# CH32V307V-R0-1v0.net
KiCad netlist of a schematic drawn in Altium Designer
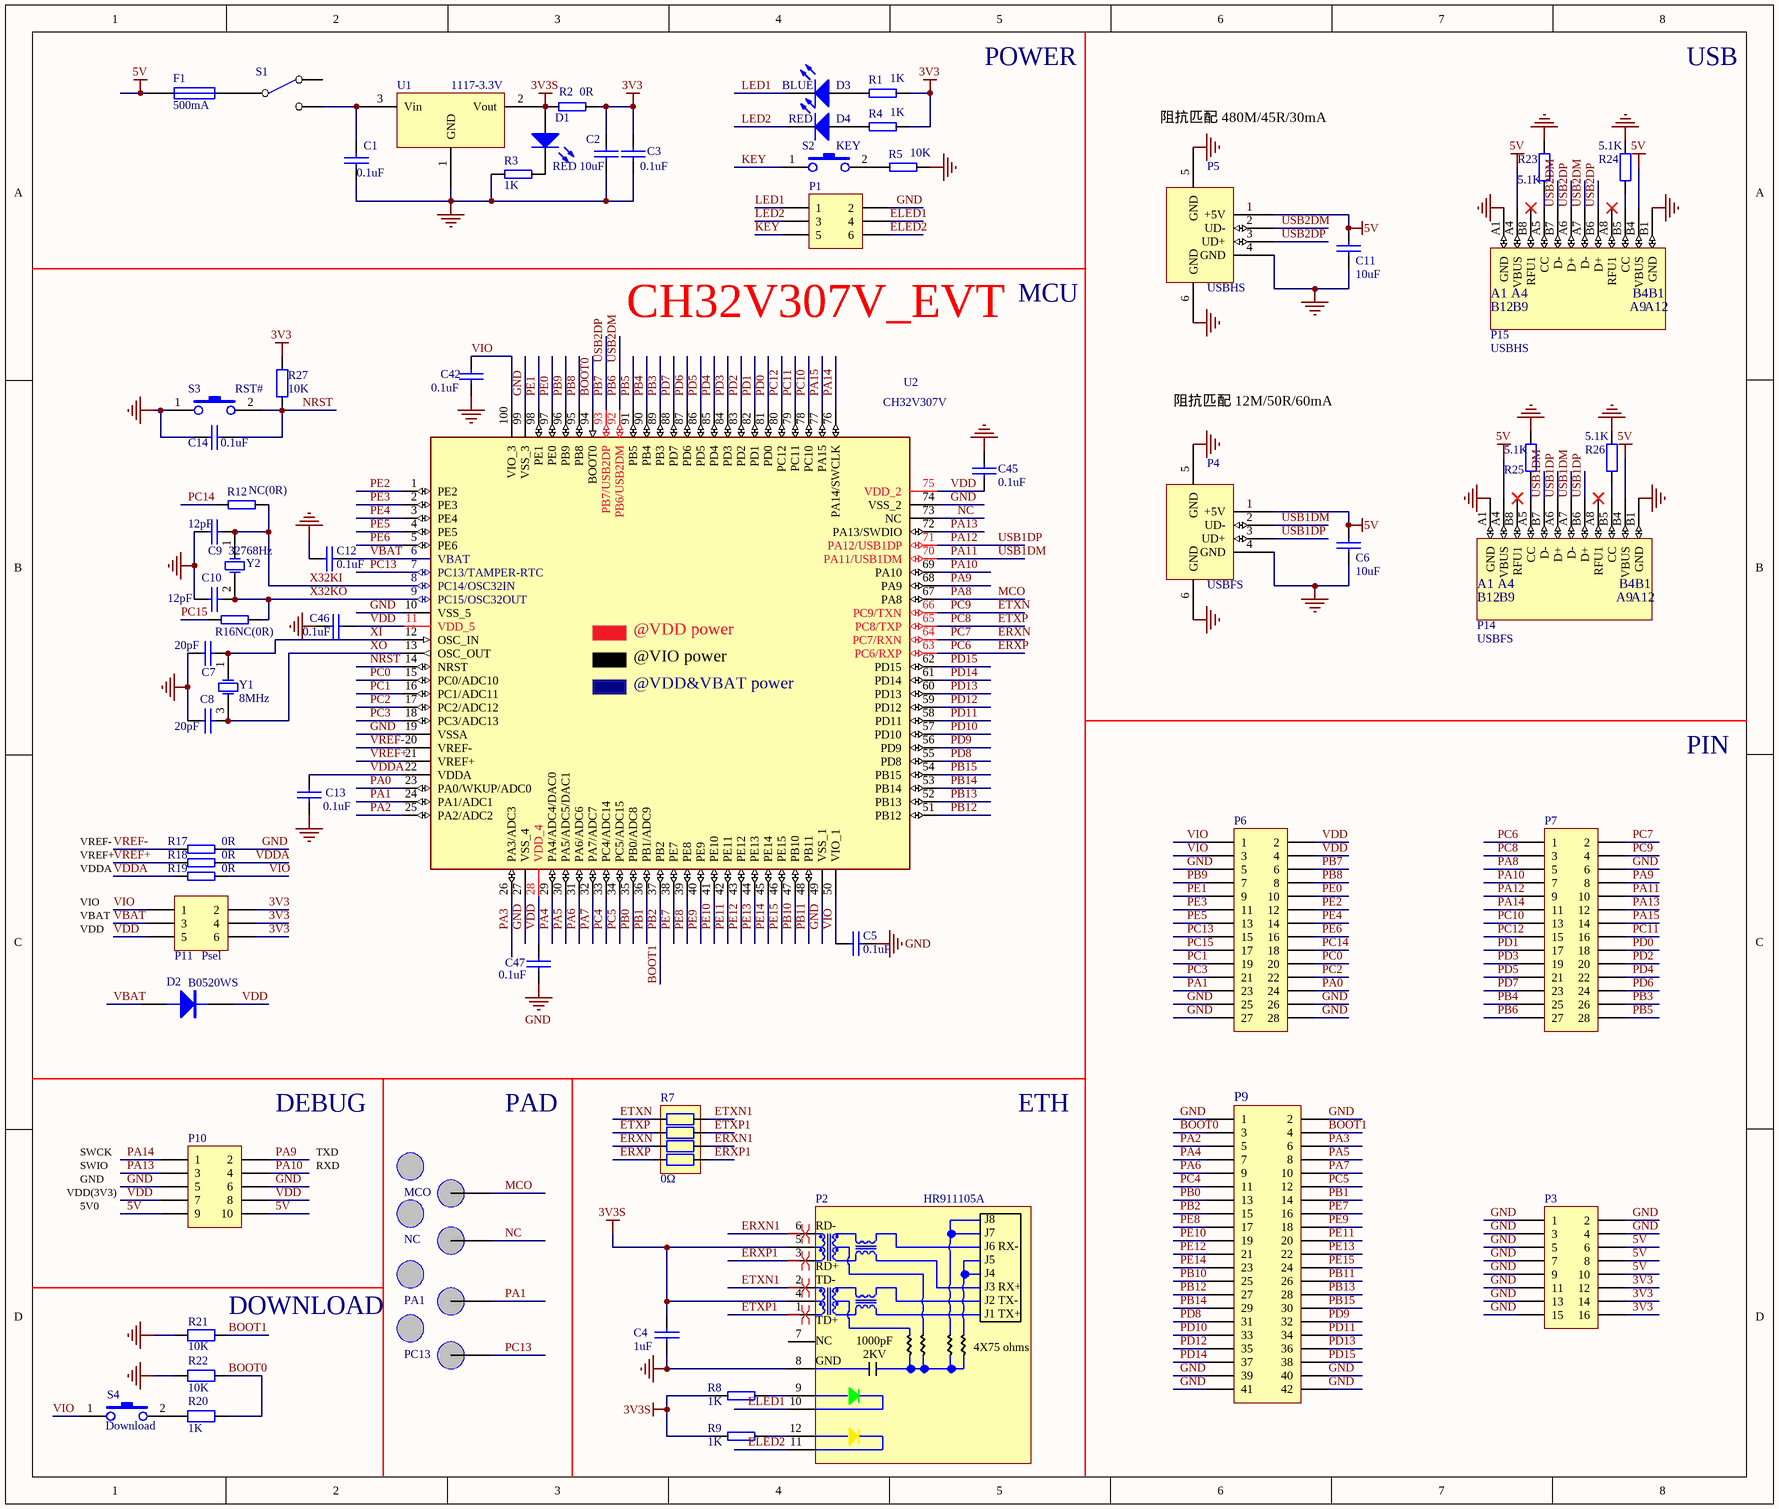
[diagram p0: CH32V307V-R0-1v0.SchDoc]

(export (version "E")
  (design (tool "Eeschema 10.0.6"))
  (components
    (comp (ref "C1")
      (value "0.1uF")
      (footprint "0603_C")
      (description "Capacitor")
      (libsource (lib "*") (part "CAP"))
    )
    (comp (ref "C2")
      (value "10uF")
      (footprint "3216_C")
      (description "Capacitor")
      (libsource (lib "*") (part "CAP"))
    )
    (comp (ref "C3")
      (value "0.1uF")
      (footprint "0603_C")
      (description "Capacitor")
      (libsource (lib "*") (part "CAP"))
    )
    (comp (ref "C4")
      (value "1uF")
      (footprint "0603_C")
      (description "Capacitor")
      (libsource (lib "*") (part "CAP"))
    )
    (comp (ref "C5")
      (value "0.1uF")
      (footprint "0603_C")
      (description "Capacitor")
      (libsource (lib "*") (part "CAP"))
    )
    (comp (ref "C6")
      (value "10uF")
      (footprint "3216_C")
      (description "Capacitor")
      (libsource (lib "") (part "CAP_1"))
    )
    (comp (ref "C7")
      (value "20pF")
      (footprint "0603_C")
      (description "Capacitor")
      (libsource (lib "*") (part "CAP"))
    )
    (comp (ref "C8")
      (value "20pF")
      (footprint "0603_C")
      (description "Capacitor")
      (libsource (lib "*") (part "CAP"))
    )
    (comp (ref "C9")
      (value "12pF")
      (footprint "0603_C")
      (description "Capacitor")
      (libsource (lib "*") (part "CAP"))
    )
    (comp (ref "C10")
      (value "12pF")
      (footprint "0603_C")
      (description "Capacitor")
      (libsource (lib "*") (part "CAP"))
    )
    (comp (ref "C11")
      (value "10uF")
      (footprint "3216_C")
      (description "Capacitor")
      (libsource (lib "") (part "CAP_1"))
    )
    (comp (ref "C12")
      (value "0.1uF")
      (footprint "0603_C")
      (description "Capacitor")
      (libsource (lib "*") (part "CAP"))
    )
    (comp (ref "C13")
      (value "0.1uF")
      (footprint "0603_C")
      (description "Capacitor")
      (libsource (lib "*") (part "CAP"))
    )
    (comp (ref "C14")
      (value "0.1uF")
      (footprint "0603_C")
      (description "Capacitor")
      (libsource (lib "") (part "CAP_1"))
    )
    (comp (ref "C42")
      (value "0.1uF")
      (footprint "0603_C")
      (description "Capacitor")
      (libsource (lib "*") (part "CAP"))
    )
    (comp (ref "C45")
      (value "0.1uF")
      (footprint "0603_C")
      (description "Capacitor")
      (libsource (lib "*") (part "CAP"))
    )
    (comp (ref "C46")
      (value "0.1uF")
      (footprint "0603_C")
      (description "Capacitor")
      (libsource (lib "*") (part "CAP"))
    )
    (comp (ref "C47")
      (value "0.1uF")
      (footprint "0603_C")
      (description "Capacitor")
      (libsource (lib "*") (part "CAP"))
    )
    (comp (ref "D1")
      (value "RED")
      (footprint "0603+")
      (description "Typical INFRARED GaAs LED")
      (fields (field (name "PUBLISHER") "Altium Limited"))
      (libsource (lib "*") (part "LED0"))
    )
    (comp (ref "D2")
      (value "B0520WS")
      (footprint "SOD-323")
      (description "Diode")
      (libsource (lib "*") (part "DIODE"))
    )
    (comp (ref "D3")
      (value "BLUE")
      (footprint "0603+")
      (description "Typical INFRARED GaAs LED")
      (fields (field (name "PUBLISHER") "Altium Limited"))
      (libsource (lib "*") (part "LED0"))
    )
    (comp (ref "D4")
      (value "RED")
      (footprint "0603+")
      (description "Typical INFRARED GaAs LED")
      (fields (field (name "PUBLISHER") "Altium Limited"))
      (libsource (lib "*") (part "LED0"))
    )
    (comp (ref "F1")
      (value "500mA")
      (footprint "0805")
      (description "Fuse")
      (libsource (lib "wch_sch_others") (part "FUSE1"))
    )
    (comp (ref "MCO")
      (value "Testpoint")
      (footprint "TESTPOINT1")
      (description "测试点")
      (libsource (lib "wch_sch_others") (part "Testpoint"))
    )
    (comp (ref "NC")
      (value "Testpoint")
      (footprint "TESTPOINT1")
      (description "测试点")
      (libsource (lib "wch_sch_others") (part "Testpoint"))
    )
    (comp (ref "P1")
      (value "IO")
      (footprint "IDC6-2.54mm")
      (description "Header, 3-Pin, Dual row, Right Angle")
      (fields (field (name "PUBLISHER") "Altium Limited"))
      (libsource (lib "Miscellaneous Connectors") (part "Header 3X2H"))
    )
    (comp (ref "P2") (value "HR911105A") (footprint "HR911105A") (libsource (lib "*") (part "HR911105A")))
    (comp (ref "P3")
      (value "Ppin")
      (footprint "IDC16-2.54mm")
      (description "Header, 8-Pin, Dual row, Right Angle")
      (fields (field (name "PUBLISHER") "Altium Limited"))
      (libsource (lib "Miscellaneous Connectors") (part "Header 8X2H"))
    )
    (comp (ref "P4")
      (value "USBFS")
      (footprint "USBAF")
      (description "USB Port")
      (libsource (lib "*") (part "USB"))
    )
    (comp (ref "P5")
      (value "USBHS")
      (footprint "USBAF")
      (description "USB Port")
      (libsource (lib "*") (part "USB"))
    )
    (comp (ref "P6")
      (value "HEADER 14x2")
      (footprint "MYPCB:IDC28-2.54MM")
      (description "Header, 14-Pin, Dual row")
      (libsource (lib "wch_sch_others") (part "HEADER 14x2"))
    )
    (comp (ref "P7")
      (value "HEADER 14x2")
      (footprint "MYPCB:IDC28-2.54MM")
      (description "Header, 14-Pin, Dual row")
      (libsource (lib "wch_sch_others") (part "HEADER 14x2"))
    )
    (comp (ref "P9")
      (value "HEADER 21x2")
      (footprint "MYPCB:IDC42-2.54MM")
      (description "Header, 21-Pin, Dual row")
      (libsource (lib "wch_sch_others") (part "HEADER 21x2"))
    )
    (comp (ref "P10")
      (value "LINK")
      (footprint "IDC10-2.54mm")
      (description "Header, 5-Pin, Dual row, Right Angle")
      (fields (field (name "PUBLISHER") "Altium Limited"))
      (libsource (lib "Miscellaneous Connectors") (part "Header 5X2H"))
    )
    (comp (ref "P11")
      (value "Psel")
      (footprint "IDC6-2.54mm")
      (description "Header, 3-Pin, Dual row, Right Angle")
      (fields (field (name "PUBLISHER") "Altium Limited"))
      (libsource (lib "Miscellaneous Connectors") (part "Header 3X2H"))
    )
    (comp (ref "P14")
      (value "USBFS")
      (footprint "TYPE-C-Receptacle-2.0")
      (libsource (lib "*") (part "TYPE-C1"))
    )
    (comp (ref "P15")
      (value "USBHS")
      (footprint "TYPE-C-Receptacle-2.0")
      (libsource (lib "*") (part "TYPE-C1"))
    )
    (comp (ref "PA1")
      (value "Testpoint")
      (footprint "TESTPOINT1")
      (description "测试点")
      (libsource (lib "wch_sch_others") (part "Testpoint"))
    )
    (comp (ref "PC13")
      (value "Testpoint")
      (footprint "TESTPOINT1")
      (description "测试点")
      (libsource (lib "wch_sch_others") (part "Testpoint"))
    )
    (comp (ref "R1") (value "1K") (footprint "0603") (libsource (lib "wch_sch_others") (part "RES")))
    (comp (ref "R2") (value "0R") (footprint "0603") (libsource (lib "wch_sch_others") (part "RES")))
    (comp (ref "R3") (value "1K") (footprint "0603") (libsource (lib "wch_sch_others") (part "RES")))
    (comp (ref "R4") (value "1K") (footprint "0603") (libsource (lib "wch_sch_others") (part "RES")))
    (comp (ref "R5") (value "10K") (footprint "0603") (libsource (lib "wch_sch_others") (part "RES")))
    (comp (ref "R7")
      (value "0Ω")
      (footprint "RCA-8P4R-0603")
      (description "贴片网络排阻")
      (fields (field (name "版权归属") "源创客"))
      (libsource (lib "wch_sch_others") (part "R-8P4R"))
    )
    (comp (ref "R8") (value "1K") (footprint "0603") (libsource (lib "wch_sch_others") (part "RES")))
    (comp (ref "R9") (value "1K") (footprint "0603") (libsource (lib "wch_sch_others") (part "RES")))
    (comp (ref "R12") (value "NC(0R)") (footprint "0603") (libsource (lib "wch_sch_others") (part "RES")))
    (comp (ref "R16") (value "NC(0R)") (footprint "0603") (libsource (lib "wch_sch_others") (part "RES")))
    (comp (ref "R17") (value "0R") (footprint "0603") (libsource (lib "*") (part "R")))
    (comp (ref "R18") (value "0R") (footprint "0603") (libsource (lib "*") (part "R")))
    (comp (ref "R19") (value "0R") (footprint "0603") (libsource (lib "*") (part "R")))
    (comp (ref "R20")
      (value "1K")
      (footprint "0603")
      (description "Resistor")
      (fields (field (name "PUBLISHER") "Altium Limited"))
      (libsource (lib "Miscellaneous Devices") (part "Res2"))
    )
    (comp (ref "R21")
      (value "10K")
      (footprint "0603")
      (description "Resistor")
      (fields (field (name "PUBLISHER") "Altium Limited"))
      (libsource (lib "Miscellaneous Devices") (part "Res2"))
    )
    (comp (ref "R22")
      (value "10K")
      (footprint "0603")
      (description "Resistor")
      (fields (field (name "PUBLISHER") "Altium Limited"))
      (libsource (lib "Miscellaneous Devices") (part "Res2"))
    )
    (comp (ref "R23")
      (value "5.1K")
      (footprint "0603")
      (description "Resistor")
      (libsource (lib "") (part "Res2_1"))
    )
    (comp (ref "R24")
      (value "5.1K")
      (footprint "0603")
      (description "Resistor")
      (libsource (lib "") (part "Res2_1"))
    )
    (comp (ref "R25")
      (value "5.1K")
      (footprint "0603")
      (description "Resistor")
      (libsource (lib "") (part "Res2_1"))
    )
    (comp (ref "R26")
      (value "5.1K")
      (footprint "0603")
      (description "Resistor")
      (libsource (lib "") (part "Res2_1"))
    )
    (comp (ref "R27")
      (value "10K")
      (footprint "0603")
      (description "Resistor")
      (fields (field (name "PUBLISHER") "Altium Limited"))
      (libsource (lib "") (part "Res2_1"))
    )
    (comp (ref "S1") (value "SW SPDT") (footprint "KEY_B") (libsource (lib "*") (part "SW SPDT")))
    (comp (ref "S2")
      (value "KEY")
      (footprint "SMD_6.1x3.65x2.5mm-KEY")
      (libsource (lib "wch_sch_others") (part "KEY1"))
    )
    (comp (ref "S3")
      (value "RST#")
      (footprint "SMD_6.1x3.65x2.5mm-KEY")
      (libsource (lib "wch_sch_others") (part "KEY1"))
    )
    (comp (ref "S4")
      (value "Download")
      (footprint "SMD_6.1x3.65x2.5mm-KEY")
      (libsource (lib "wch_sch_others") (part "KEY1"))
    )
    (comp (ref "U1")
      (value "1117-3.3V")
      (footprint "SOT-223")
      (libsource (lib "wch_sch_others") (part "1117-3.3V"))
    )
    (comp (ref "U2")
      (value "CH32V307V")
      (footprint "LQFP100")
      (description "RISC-V FPU MCU, 144MHz, USB_480M，USB OTG,1000M Ethernet MAC, 2*CAN")
      (libsource (lib "CHXXX") (part "CH32V307V"))
    )
    (comp (ref "Y1")
      (value "8MHz")
      (footprint "XT3225")
      (description "Crystal Oscillator")
      (fields (field (name "PUBLISHER") "Altium Limited"))
      (libsource (lib "*") (part "XTAL"))
    )
    (comp (ref "Y2")
      (value "32768Hz")
      (footprint "FC-135")
      (description "Crystal Oscillator")
      (fields (field (name "PUBLISHER") "Altium Limited"))
      (libsource (lib "") (part "XTAL_1"))
    )
  )
  (nets
    (net (code "2") (name "/BOOT0") (class "Default")
      (node (ref "P9") (pin "3") (pinfunction "3_3") (pintype "passive"))
      (node (ref "R20") (pin "1") (pinfunction "1_1") (pintype "passive"))
      (node (ref "R22") (pin "1") (pinfunction "1_1") (pintype "passive"))
      (node (ref "U2") (pin "94") (pinfunction "BOOT0_94") (pintype "input"))
    )
    (net (code "3") (name "/BOOT1") (class "Default")
      (node (ref "P9") (pin "15") (pinfunction "15_15") (pintype "passive"))
      (node (ref "P9") (pin "4") (pinfunction "4_4") (pintype "passive"))
      (node (ref "R21") (pin "1") (pinfunction "1_1") (pintype "passive"))
      (node (ref "U2") (pin "37") (pinfunction "PB2_37") (pintype "bidirectional"))
    )
    (net (code "4") (name "/ELED1") (class "Default")
      (node (ref "P1") (pin "4") (pinfunction "4_4") (pintype "passive"))
      (node (ref "P2") (pin "10") (pintype "passive"))
    )
    (net (code "5") (name "/ELED2") (class "Default")
      (node (ref "P1") (pin "6") (pinfunction "6_6") (pintype "passive"))
      (node (ref "P2") (pin "11") (pintype "passive"))
    )
    (net (code "6") (name "/ERXN") (class "Default")
      (node (ref "P7") (pin "2") (pinfunction "2_2") (pintype "passive"))
      (node (ref "R7") (pin "3") (pinfunction "3_3") (pintype "passive"))
      (node (ref "U2") (pin "64") (pinfunction "PC7/RXN_64") (pintype "bidirectional"))
    )
    (net (code "7") (name "/ERXN1") (class "Default")
      (node (ref "P2") (pin "6") (pintype "passive"))
      (node (ref "R7") (pin "6") (pinfunction "6_6") (pintype "passive"))
    )
    (net (code "8") (name "/ERXP") (class "Default")
      (node (ref "P7") (pin "1") (pinfunction "1_1") (pintype "passive"))
      (node (ref "R7") (pin "4") (pinfunction "4_4") (pintype "passive"))
      (node (ref "U2") (pin "63") (pinfunction "PC6/RXP_63") (pintype "bidirectional"))
    )
    (net (code "9") (name "/ERXP1") (class "Default")
      (node (ref "P2") (pin "3") (pintype "passive"))
      (node (ref "R7") (pin "5") (pinfunction "5_5") (pintype "passive"))
    )
    (net (code "10") (name "/ETXN") (class "Default")
      (node (ref "P7") (pin "4") (pinfunction "4_4") (pintype "passive"))
      (node (ref "R7") (pin "1") (pinfunction "1_1") (pintype "passive"))
      (node (ref "U2") (pin "66") (pinfunction "PC9/TXN_66") (pintype "bidirectional"))
    )
    (net (code "11") (name "/ETXN1") (class "Default")
      (node (ref "P2") (pin "2") (pintype "passive"))
      (node (ref "R7") (pin "8") (pinfunction "8_8") (pintype "passive"))
    )
    (net (code "12") (name "/ETXP") (class "Default")
      (node (ref "P7") (pin "3") (pinfunction "3_3") (pintype "passive"))
      (node (ref "R7") (pin "2") (pinfunction "2_2") (pintype "passive"))
      (node (ref "U2") (pin "65") (pinfunction "PC8/TXP_65") (pintype "bidirectional"))
    )
    (net (code "13") (name "/ETXP1") (class "Default")
      (node (ref "P2") (pin "1") (pintype "passive"))
      (node (ref "R7") (pin "7") (pinfunction "7_7") (pintype "passive"))
    )
    (net (code "14") (name "/KEY") (class "Default")
      (node (ref "P1") (pin "5") (pinfunction "5_5") (pintype "passive"))
      (node (ref "S2") (pin "1") (pinfunction "1_1") (pintype "passive"))
    )
    (net (code "15") (name "/LED1") (class "Default")
      (node (ref "D3") (pin "2") (pinfunction "K_2") (pintype "passive"))
      (node (ref "P1") (pin "1") (pinfunction "1_1") (pintype "passive"))
    )
    (net (code "16") (name "/LED2") (class "Default")
      (node (ref "D4") (pin "2") (pinfunction "K_2") (pintype "passive"))
      (node (ref "P1") (pin "3") (pinfunction "3_3") (pintype "passive"))
    )
    (net (code "17") (name "/MCO") (class "Default")
      (node (ref "MCO") (pin "1") (pinfunction "point_1") (pintype "passive"))
      (node (ref "P7") (pin "5") (pinfunction "5_5") (pintype "passive"))
      (node (ref "U2") (pin "67") (pinfunction "PA8_67") (pintype "bidirectional"))
    )
    (net (code "18") (name "/NC") (class "Default")
      (node (ref "NC") (pin "1") (pinfunction "point_1") (pintype "passive"))
      (node (ref "U2") (pin "73") (pinfunction "NC_73") (pintype "tri_state"))
    )
    (net (code "19") (name "/NRST") (class "Default")
      (node (ref "C14") (pin "2") (pinfunction "2_2") (pintype "passive"))
      (node (ref "R27") (pin "1") (pinfunction "1_1") (pintype "passive"))
      (node (ref "S3") (pin "2") (pinfunction "2_2") (pintype "passive"))
      (node (ref "U2") (pin "14") (pinfunction "NRST_14") (pintype "bidirectional"))
    )
    (net (code "20") (name "/PA0") (class "Default")
      (node (ref "P6") (pin "24") (pinfunction "24_24") (pintype "passive"))
      (node (ref "U2") (pin "23") (pinfunction "PA0/WKUP/ADC0_23") (pintype "bidirectional"))
    )
    (net (code "21") (name "/PA1") (class "Default")
      (node (ref "P6") (pin "23") (pinfunction "23_23") (pintype "passive"))
      (node (ref "PA1") (pin "1") (pinfunction "point_1") (pintype "passive"))
      (node (ref "U2") (pin "24") (pinfunction "PA1/ADC1_24") (pintype "bidirectional"))
    )
    (net (code "22") (name "/PA2") (class "Default")
      (node (ref "P9") (pin "5") (pinfunction "5_5") (pintype "passive"))
      (node (ref "U2") (pin "25") (pinfunction "PA2/ADC2_25") (pintype "bidirectional"))
    )
    (net (code "23") (name "/PA3") (class "Default")
      (node (ref "P9") (pin "6") (pinfunction "6_6") (pintype "passive"))
      (node (ref "U2") (pin "26") (pinfunction "PA3/ADC3_26") (pintype "bidirectional"))
    )
    (net (code "24") (name "/PA4") (class "Default")
      (node (ref "P9") (pin "7") (pinfunction "7_7") (pintype "passive"))
      (node (ref "U2") (pin "29") (pinfunction "PA4/ADC4/DAC0_29") (pintype "bidirectional"))
    )
    (net (code "25") (name "/PA5") (class "Default")
      (node (ref "P9") (pin "8") (pinfunction "8_8") (pintype "passive"))
      (node (ref "U2") (pin "30") (pinfunction "PA5/ADC5/DAC1_30") (pintype "bidirectional"))
    )
    (net (code "26") (name "/PA6") (class "Default")
      (node (ref "P9") (pin "9") (pinfunction "9_9") (pintype "passive"))
      (node (ref "U2") (pin "31") (pinfunction "PA6/ADC6_31") (pintype "bidirectional"))
    )
    (net (code "27") (name "/PA7") (class "Default")
      (node (ref "P9") (pin "10") (pinfunction "10_10") (pintype "passive"))
      (node (ref "U2") (pin "32") (pinfunction "PA7/ADC7_32") (pintype "bidirectional"))
    )
    (net (code "28") (name "/PA9") (class "Default")
      (node (ref "P10") (pin "2") (pinfunction "2_2") (pintype "passive"))
      (node (ref "P7") (pin "8") (pinfunction "8_8") (pintype "passive"))
      (node (ref "U2") (pin "68") (pinfunction "PA9_68") (pintype "bidirectional"))
    )
    (net (code "29") (name "/PA10") (class "Default")
      (node (ref "P10") (pin "4") (pinfunction "4_4") (pintype "passive"))
      (node (ref "P7") (pin "7") (pinfunction "7_7") (pintype "passive"))
      (node (ref "U2") (pin "69") (pinfunction "PA10_69") (pintype "bidirectional"))
    )
    (net (code "30") (name "/PA11") (class "Default")
      (node (ref "P14") (pin "A7") (pinfunction "D-_A7") (pintype "bidirectional"))
      (node (ref "P14") (pin "B7") (pinfunction "D-_B7") (pintype "bidirectional"))
      (node (ref "P4") (pin "2") (pinfunction "UD-_2") (pintype "bidirectional"))
      (node (ref "P7") (pin "10") (pinfunction "10_10") (pintype "passive"))
      (node (ref "U2") (pin "70") (pinfunction "PA11/USB1DM_70") (pintype "bidirectional"))
    )
    (net (code "31") (name "/PA12") (class "Default")
      (node (ref "P14") (pin "A6") (pinfunction "D+_A6") (pintype "bidirectional"))
      (node (ref "P14") (pin "B6") (pinfunction "D+_B6") (pintype "bidirectional"))
      (node (ref "P4") (pin "3") (pinfunction "UD+_3") (pintype "bidirectional"))
      (node (ref "P7") (pin "9") (pinfunction "9_9") (pintype "passive"))
      (node (ref "U2") (pin "71") (pinfunction "PA12/USB1DP_71") (pintype "bidirectional"))
    )
    (net (code "32") (name "/PA13") (class "Default")
      (node (ref "P10") (pin "3") (pinfunction "3_3") (pintype "passive"))
      (node (ref "P7") (pin "12") (pinfunction "12_12") (pintype "passive"))
      (node (ref "U2") (pin "72") (pinfunction "PA13/SWDIO_72") (pintype "bidirectional"))
    )
    (net (code "33") (name "/PA14") (class "Default")
      (node (ref "P10") (pin "1") (pinfunction "1_1") (pintype "passive"))
      (node (ref "P7") (pin "11") (pinfunction "11_11") (pintype "passive"))
      (node (ref "U2") (pin "76") (pinfunction "PA14/SWCLK_76") (pintype "bidirectional"))
    )
    (net (code "34") (name "/PA15") (class "Default")
      (node (ref "P7") (pin "14") (pinfunction "14_14") (pintype "passive"))
      (node (ref "U2") (pin "77") (pinfunction "PA15_77") (pintype "bidirectional"))
    )
    (net (code "35") (name "/PB0") (class "Default")
      (node (ref "P9") (pin "13") (pinfunction "13_13") (pintype "passive"))
      (node (ref "U2") (pin "35") (pinfunction "PB0/ADC8_35") (pintype "bidirectional"))
    )
    (net (code "36") (name "/PB1") (class "Default")
      (node (ref "P9") (pin "14") (pinfunction "14_14") (pintype "passive"))
      (node (ref "U2") (pin "36") (pinfunction "PB1/ADC9_36") (pintype "bidirectional"))
    )
    (net (code "37") (name "/PB3") (class "Default")
      (node (ref "P7") (pin "26") (pinfunction "26_26") (pintype "passive"))
      (node (ref "U2") (pin "89") (pinfunction "PB3_89") (pintype "bidirectional"))
    )
    (net (code "38") (name "/PB4") (class "Default")
      (node (ref "P7") (pin "25") (pinfunction "25_25") (pintype "passive"))
      (node (ref "U2") (pin "90") (pinfunction "PB4_90") (pintype "bidirectional"))
    )
    (net (code "39") (name "/PB5") (class "Default")
      (node (ref "P7") (pin "28") (pinfunction "28_28") (pintype "passive"))
      (node (ref "U2") (pin "91") (pinfunction "PB5_91") (pintype "bidirectional"))
    )
    (net (code "40") (name "/PB6") (class "Default")
      (node (ref "P15") (pin "A7") (pinfunction "D-_A7") (pintype "bidirectional"))
      (node (ref "P15") (pin "B7") (pinfunction "D-_B7") (pintype "bidirectional"))
      (node (ref "P5") (pin "2") (pinfunction "UD-_2") (pintype "bidirectional"))
      (node (ref "P7") (pin "27") (pinfunction "27_27") (pintype "passive"))
      (node (ref "U2") (pin "92") (pinfunction "PB6/USB2DM_92") (pintype "bidirectional"))
    )
    (net (code "41") (name "/PB7") (class "Default")
      (node (ref "P15") (pin "A6") (pinfunction "D+_A6") (pintype "bidirectional"))
      (node (ref "P15") (pin "B6") (pinfunction "D+_B6") (pintype "bidirectional"))
      (node (ref "P5") (pin "3") (pinfunction "UD+_3") (pintype "bidirectional"))
      (node (ref "P6") (pin "6") (pinfunction "6_6") (pintype "passive"))
      (node (ref "U2") (pin "93") (pinfunction "PB7/USB2DP_93") (pintype "bidirectional"))
    )
    (net (code "42") (name "/PB8") (class "Default")
      (node (ref "P6") (pin "8") (pinfunction "8_8") (pintype "passive"))
      (node (ref "U2") (pin "95") (pinfunction "PB8_95") (pintype "bidirectional"))
    )
    (net (code "43") (name "/PB9") (class "Default")
      (node (ref "P6") (pin "7") (pinfunction "7_7") (pintype "passive"))
      (node (ref "U2") (pin "96") (pinfunction "PB9_96") (pintype "bidirectional"))
    )
    (net (code "44") (name "/PB10") (class "Default")
      (node (ref "P9") (pin "25") (pinfunction "25_25") (pintype "passive"))
      (node (ref "U2") (pin "47") (pinfunction "PB10_47") (pintype "bidirectional"))
    )
    (net (code "45") (name "/PB11") (class "Default")
      (node (ref "P9") (pin "26") (pinfunction "26_26") (pintype "passive"))
      (node (ref "U2") (pin "48") (pinfunction "PB11_48") (pintype "bidirectional"))
    )
    (net (code "46") (name "/PB12") (class "Default")
      (node (ref "P9") (pin "27") (pinfunction "27_27") (pintype "passive"))
      (node (ref "U2") (pin "51") (pinfunction "PB12_51") (pintype "bidirectional"))
    )
    (net (code "47") (name "/PB13") (class "Default")
      (node (ref "P9") (pin "28") (pinfunction "28_28") (pintype "passive"))
      (node (ref "U2") (pin "52") (pinfunction "PB13_52") (pintype "bidirectional"))
    )
    (net (code "48") (name "/PB14") (class "Default")
      (node (ref "P9") (pin "29") (pinfunction "29_29") (pintype "passive"))
      (node (ref "U2") (pin "53") (pinfunction "PB14_53") (pintype "bidirectional"))
    )
    (net (code "49") (name "/PB15") (class "Default")
      (node (ref "P9") (pin "30") (pinfunction "30_30") (pintype "passive"))
      (node (ref "U2") (pin "54") (pinfunction "PB15_54") (pintype "bidirectional"))
    )
    (net (code "50") (name "/PC0") (class "Default")
      (node (ref "P6") (pin "20") (pinfunction "20_20") (pintype "passive"))
      (node (ref "U2") (pin "15") (pinfunction "PC0/ADC10_15") (pintype "bidirectional"))
    )
    (net (code "51") (name "/PC1") (class "Default")
      (node (ref "P6") (pin "19") (pinfunction "19_19") (pintype "passive"))
      (node (ref "U2") (pin "16") (pinfunction "PC1/ADC11_16") (pintype "bidirectional"))
    )
    (net (code "52") (name "/PC2") (class "Default")
      (node (ref "P6") (pin "22") (pinfunction "22_22") (pintype "passive"))
      (node (ref "U2") (pin "17") (pinfunction "PC2/ADC12_17") (pintype "bidirectional"))
    )
    (net (code "53") (name "/PC3") (class "Default")
      (node (ref "P6") (pin "21") (pinfunction "21_21") (pintype "passive"))
      (node (ref "U2") (pin "18") (pinfunction "PC3/ADC13_18") (pintype "bidirectional"))
    )
    (net (code "54") (name "/PC4") (class "Default")
      (node (ref "P9") (pin "11") (pinfunction "11_11") (pintype "passive"))
      (node (ref "U2") (pin "33") (pinfunction "PC4/ADC14_33") (pintype "bidirectional"))
    )
    (net (code "55") (name "/PC5") (class "Default")
      (node (ref "P9") (pin "12") (pinfunction "12_12") (pintype "passive"))
      (node (ref "U2") (pin "34") (pinfunction "PC5/ADC15_34") (pintype "bidirectional"))
    )
    (net (code "56") (name "/PC10") (class "Default")
      (node (ref "P7") (pin "13") (pinfunction "13_13") (pintype "passive"))
      (node (ref "U2") (pin "78") (pinfunction "PC10_78") (pintype "bidirectional"))
    )
    (net (code "57") (name "/PC11") (class "Default")
      (node (ref "P7") (pin "16") (pinfunction "16_16") (pintype "passive"))
      (node (ref "U2") (pin "79") (pinfunction "PC11_79") (pintype "bidirectional"))
    )
    (net (code "58") (name "/PC12") (class "Default")
      (node (ref "P7") (pin "15") (pinfunction "15_15") (pintype "passive"))
      (node (ref "U2") (pin "80") (pinfunction "PC12_80") (pintype "bidirectional"))
    )
    (net (code "59") (name "/PC13") (class "Default")
      (node (ref "P6") (pin "15") (pinfunction "15_15") (pintype "passive"))
      (node (ref "PC13") (pin "1") (pinfunction "point_1") (pintype "passive"))
      (node (ref "U2") (pin "7") (pinfunction "PC13/TAMPER-RTC_7") (pintype "bidirectional"))
    )
    (net (code "60") (name "/PC14") (class "Default")
      (node (ref "P6") (pin "18") (pinfunction "18_18") (pintype "passive"))
      (node (ref "R12") (pin "1") (pintype "passive"))
    )
    (net (code "61") (name "/PC15") (class "Default")
      (node (ref "P6") (pin "17") (pinfunction "17_17") (pintype "passive"))
      (node (ref "R16") (pin "1") (pintype "passive"))
    )
    (net (code "62") (name "/PD0") (class "Default")
      (node (ref "P7") (pin "18") (pinfunction "18_18") (pintype "passive"))
      (node (ref "U2") (pin "81") (pinfunction "PD0_81") (pintype "bidirectional"))
    )
    (net (code "63") (name "/PD1") (class "Default")
      (node (ref "P7") (pin "17") (pinfunction "17_17") (pintype "passive"))
      (node (ref "U2") (pin "82") (pinfunction "PD1_82") (pintype "bidirectional"))
    )
    (net (code "64") (name "/PD2") (class "Default")
      (node (ref "P7") (pin "20") (pinfunction "20_20") (pintype "passive"))
      (node (ref "U2") (pin "83") (pinfunction "PD2_83") (pintype "bidirectional"))
    )
    (net (code "65") (name "/PD3") (class "Default")
      (node (ref "P7") (pin "19") (pinfunction "19_19") (pintype "passive"))
      (node (ref "U2") (pin "84") (pinfunction "PD3_84") (pintype "bidirectional"))
    )
    (net (code "66") (name "/PD4") (class "Default")
      (node (ref "P7") (pin "22") (pinfunction "22_22") (pintype "passive"))
      (node (ref "U2") (pin "85") (pinfunction "PD4_85") (pintype "bidirectional"))
    )
    (net (code "67") (name "/PD5") (class "Default")
      (node (ref "P7") (pin "21") (pinfunction "21_21") (pintype "passive"))
      (node (ref "U2") (pin "86") (pinfunction "PD5_86") (pintype "bidirectional"))
    )
    (net (code "68") (name "/PD6") (class "Default")
      (node (ref "P7") (pin "24") (pinfunction "24_24") (pintype "passive"))
      (node (ref "U2") (pin "87") (pinfunction "PD6_87") (pintype "bidirectional"))
    )
    (net (code "69") (name "/PD7") (class "Default")
      (node (ref "P7") (pin "23") (pinfunction "23_23") (pintype "passive"))
      (node (ref "U2") (pin "88") (pinfunction "PD7_88") (pintype "bidirectional"))
    )
    (net (code "70") (name "/PD8") (class "Default")
      (node (ref "P9") (pin "31") (pinfunction "31_31") (pintype "passive"))
      (node (ref "U2") (pin "55") (pinfunction "PD8_55") (pintype "bidirectional"))
    )
    (net (code "71") (name "/PD9") (class "Default")
      (node (ref "P9") (pin "32") (pinfunction "32_32") (pintype "passive"))
      (node (ref "U2") (pin "56") (pinfunction "PD9_56") (pintype "bidirectional"))
    )
    (net (code "72") (name "/PD10") (class "Default")
      (node (ref "P9") (pin "33") (pinfunction "33_33") (pintype "passive"))
      (node (ref "U2") (pin "57") (pinfunction "PD10_57") (pintype "bidirectional"))
    )
    (net (code "73") (name "/PD11") (class "Default")
      (node (ref "P9") (pin "34") (pinfunction "34_34") (pintype "passive"))
      (node (ref "U2") (pin "58") (pinfunction "PD11_58") (pintype "bidirectional"))
    )
    (net (code "74") (name "/PD12") (class "Default")
      (node (ref "P9") (pin "35") (pinfunction "35_35") (pintype "passive"))
      (node (ref "U2") (pin "59") (pinfunction "PD12_59") (pintype "bidirectional"))
    )
    (net (code "75") (name "/PD13") (class "Default")
      (node (ref "P9") (pin "36") (pinfunction "36_36") (pintype "passive"))
      (node (ref "U2") (pin "60") (pinfunction "PD13_60") (pintype "bidirectional"))
    )
    (net (code "76") (name "/PD14") (class "Default")
      (node (ref "P9") (pin "37") (pinfunction "37_37") (pintype "passive"))
      (node (ref "U2") (pin "61") (pinfunction "PD14_61") (pintype "bidirectional"))
    )
    (net (code "77") (name "/PD15") (class "Default")
      (node (ref "P9") (pin "38") (pinfunction "38_38") (pintype "passive"))
      (node (ref "U2") (pin "62") (pinfunction "PD15_62") (pintype "bidirectional"))
    )
    (net (code "78") (name "/PE0") (class "Default")
      (node (ref "P6") (pin "10") (pinfunction "10_10") (pintype "passive"))
      (node (ref "U2") (pin "97") (pinfunction "PE0_97") (pintype "bidirectional"))
    )
    (net (code "79") (name "/PE1") (class "Default")
      (node (ref "P6") (pin "9") (pinfunction "9_9") (pintype "passive"))
      (node (ref "U2") (pin "98") (pinfunction "PE1_98") (pintype "bidirectional"))
    )
    (net (code "80") (name "/PE2") (class "Default")
      (node (ref "P6") (pin "12") (pinfunction "12_12") (pintype "passive"))
      (node (ref "U2") (pin "1") (pinfunction "PE2_1") (pintype "bidirectional"))
    )
    (net (code "81") (name "/PE3") (class "Default")
      (node (ref "P6") (pin "11") (pinfunction "11_11") (pintype "passive"))
      (node (ref "U2") (pin "2") (pinfunction "PE3_2") (pintype "bidirectional"))
    )
    (net (code "82") (name "/PE4") (class "Default")
      (node (ref "P6") (pin "14") (pinfunction "14_14") (pintype "passive"))
      (node (ref "U2") (pin "3") (pinfunction "PE4_3") (pintype "bidirectional"))
    )
    (net (code "83") (name "/PE5") (class "Default")
      (node (ref "P6") (pin "13") (pinfunction "13_13") (pintype "passive"))
      (node (ref "U2") (pin "4") (pinfunction "PE5_4") (pintype "bidirectional"))
    )
    (net (code "84") (name "/PE6") (class "Default")
      (node (ref "P6") (pin "16") (pinfunction "16_16") (pintype "passive"))
      (node (ref "U2") (pin "5") (pinfunction "PE6_5") (pintype "bidirectional"))
    )
    (net (code "85") (name "/PE7") (class "Default")
      (node (ref "P9") (pin "16") (pinfunction "16_16") (pintype "passive"))
      (node (ref "U2") (pin "38") (pinfunction "PE7_38") (pintype "bidirectional"))
    )
    (net (code "86") (name "/PE8") (class "Default")
      (node (ref "P9") (pin "17") (pinfunction "17_17") (pintype "passive"))
      (node (ref "U2") (pin "39") (pinfunction "PE8_39") (pintype "bidirectional"))
    )
    (net (code "87") (name "/PE9") (class "Default")
      (node (ref "P9") (pin "18") (pinfunction "18_18") (pintype "passive"))
      (node (ref "U2") (pin "40") (pinfunction "PE9_40") (pintype "bidirectional"))
    )
    (net (code "88") (name "/PE10") (class "Default")
      (node (ref "P9") (pin "19") (pinfunction "19_19") (pintype "passive"))
      (node (ref "U2") (pin "41") (pinfunction "PE10_41") (pintype "bidirectional"))
    )
    (net (code "89") (name "/PE11") (class "Default")
      (node (ref "P9") (pin "20") (pinfunction "20_20") (pintype "passive"))
      (node (ref "U2") (pin "42") (pinfunction "PE11_42") (pintype "bidirectional"))
    )
    (net (code "90") (name "/PE12") (class "Default")
      (node (ref "P9") (pin "21") (pinfunction "21_21") (pintype "passive"))
      (node (ref "U2") (pin "43") (pinfunction "PE12_43") (pintype "bidirectional"))
    )
    (net (code "91") (name "/PE13") (class "Default")
      (node (ref "P9") (pin "22") (pinfunction "22_22") (pintype "passive"))
      (node (ref "U2") (pin "44") (pinfunction "PE13_44") (pintype "bidirectional"))
    )
    (net (code "92") (name "/PE14") (class "Default")
      (node (ref "P9") (pin "23") (pinfunction "23_23") (pintype "passive"))
      (node (ref "U2") (pin "45") (pinfunction "PE14_45") (pintype "bidirectional"))
    )
    (net (code "93") (name "/PE15") (class "Default")
      (node (ref "P9") (pin "24") (pinfunction "24_24") (pintype "passive"))
      (node (ref "U2") (pin "46") (pinfunction "PE15_46") (pintype "bidirectional"))
    )
    (net (code "94") (name "/VBAT") (class "Default")
      (node (ref "C12") (pin "2") (pinfunction "2_2") (pintype "passive"))
      (node (ref "D2") (pin "1") (pinfunction "A_1") (pintype "passive"))
      (node (ref "P11") (pin "3") (pinfunction "3_3") (pintype "passive"))
      (node (ref "U2") (pin "6") (pinfunction "VBAT_6") (pintype "power_in"))
    )
    (net (code "95") (name "/VDD") (class "Default")
      (node (ref "C45") (pin "1") (pinfunction "1_1") (pintype "passive"))
      (node (ref "C46") (pin "1") (pinfunction "1_1") (pintype "passive"))
      (node (ref "C47") (pin "2") (pinfunction "2_2") (pintype "passive"))
      (node (ref "D2") (pin "2") (pinfunction "K_2") (pintype "passive"))
      (node (ref "P10") (pin "7") (pinfunction "7_7") (pintype "passive"))
      (node (ref "P10") (pin "8") (pinfunction "8_8") (pintype "passive"))
      (node (ref "P11") (pin "5") (pinfunction "5_5") (pintype "passive"))
      (node (ref "P6") (pin "2") (pinfunction "2_2") (pintype "passive"))
      (node (ref "P6") (pin "4") (pinfunction "4_4") (pintype "passive"))
      (node (ref "U2") (pin "11") (pinfunction "VDD_5_11") (pintype "power_in"))
      (node (ref "U2") (pin "28") (pinfunction "VDD_4_28") (pintype "power_in"))
      (node (ref "U2") (pin "75") (pinfunction "VDD_2_75") (pintype "power_in"))
    )
    (net (code "96") (name "/VDDA") (class "Default")
      (node (ref "C13") (pin "1") (pinfunction "1_1") (pintype "passive"))
      (node (ref "R18") (pin "1") (pinfunction "1_1") (pintype "passive"))
      (node (ref "R19") (pin "2") (pinfunction "2_2") (pintype "passive"))
      (node (ref "U2") (pin "22") (pinfunction "VDDA_22") (pintype "power_in"))
    )
    (net (code "97") (name "/VIO") (class "Default")
      (node (ref "C42") (pin "2") (pinfunction "2_2") (pintype "passive"))
      (node (ref "C5") (pin "1") (pinfunction "1_1") (pintype "passive"))
      (node (ref "P11") (pin "1") (pinfunction "1_1") (pintype "passive"))
      (node (ref "P6") (pin "1") (pinfunction "1_1") (pintype "passive"))
      (node (ref "P6") (pin "3") (pinfunction "3_3") (pintype "passive"))
      (node (ref "R19") (pin "1") (pinfunction "1_1") (pintype "passive"))
      (node (ref "S4") (pin "1") (pinfunction "1_1") (pintype "passive"))
      (node (ref "U2") (pin "100") (pinfunction "VIO_3_100") (pintype "power_in"))
      (node (ref "U2") (pin "50") (pinfunction "VIO_1_50") (pintype "power_in"))
    )
    (net (code "98") (name "/VREF+") (class "Default")
      (node (ref "R18") (pin "2") (pinfunction "2_2") (pintype "passive"))
      (node (ref "U2") (pin "21") (pinfunction "VREF+_21") (pintype "power_in"))
    )
    (net (code "99") (name "/VREF-") (class "Default")
      (node (ref "R17") (pin "2") (pinfunction "2_2") (pintype "passive"))
      (node (ref "U2") (pin "20") (pinfunction "VREF-_20") (pintype "power_in"))
    )
    (net (code "100") (name "/X32KI") (class "Default")
      (node (ref "C9") (pin "2") (pinfunction "2_2") (pintype "passive"))
      (node (ref "R12") (pin "2") (pintype "passive"))
      (node (ref "U2") (pin "8") (pinfunction "PC14/OSC32IN_8") (pintype "bidirectional"))
      (node (ref "Y2") (pin "1") (pinfunction "OSC1_1") (pintype "passive"))
    )
    (net (code "101") (name "/X32KO") (class "Default")
      (node (ref "C10") (pin "2") (pinfunction "2_2") (pintype "passive"))
      (node (ref "R16") (pin "2") (pintype "passive"))
      (node (ref "U2") (pin "9") (pinfunction "PC15/OSC32OUT_9") (pintype "bidirectional"))
      (node (ref "Y2") (pin "2") (pinfunction "OSC2_2") (pintype "passive"))
    )
    (net (code "102") (name "/XI") (class "Default")
      (node (ref "C7") (pin "2") (pinfunction "2_2") (pintype "passive"))
      (node (ref "U2") (pin "12") (pinfunction "OSC_IN_12") (pintype "input"))
      (node (ref "Y1") (pin "1") (pinfunction "OSC1_1") (pintype "passive"))
    )
    (net (code "103") (name "/XO") (class "Default")
      (node (ref "C8") (pin "2") (pinfunction "2_2") (pintype "passive"))
      (node (ref "U2") (pin "13") (pinfunction "OSC_OUT_13") (pintype "output"))
      (node (ref "Y1") (pin "3") (pinfunction "OSC2_3") (pintype "passive"))
    )
    (net (code "104") (name "3V3") (class "Default")
      (node (ref "C2") (pin "1") (pinfunction "1_1") (pintype "passive"))
      (node (ref "C3") (pin "1") (pinfunction "1_1") (pintype "passive"))
      (node (ref "P11") (pin "2") (pinfunction "2_2") (pintype "passive"))
      (node (ref "P11") (pin "4") (pinfunction "4_4") (pintype "passive"))
      (node (ref "P11") (pin "6") (pinfunction "6_6") (pintype "passive"))
      (node (ref "P3") (pin "12") (pinfunction "12_12") (pintype "passive"))
      (node (ref "P3") (pin "14") (pinfunction "14_14") (pintype "passive"))
      (node (ref "P3") (pin "16") (pinfunction "16_16") (pintype "passive"))
      (node (ref "R1") (pin "1") (pintype "passive"))
      (node (ref "R2") (pin "1") (pintype "passive"))
      (node (ref "R27") (pin "2") (pinfunction "2_2") (pintype "passive"))
      (node (ref "R4") (pin "1") (pintype "passive"))
    )
    (net (code "105") (name "3V3S") (class "Default")
      (node (ref "C4") (pin "2") (pinfunction "2_2") (pintype "passive"))
      (node (ref "D1") (pin "1") (pinfunction "A_1") (pintype "passive"))
      (node (ref "P2") (pin "4") (pintype "passive"))
      (node (ref "P2") (pin "5") (pintype "passive"))
      (node (ref "R2") (pin "2") (pintype "passive"))
      (node (ref "R8") (pin "1") (pintype "passive"))
      (node (ref "R9") (pin "1") (pintype "passive"))
      (node (ref "U1") (pin "2") (pinfunction "Vout_2") (pintype "passive"))
    )
    (net (code "106") (name "5V") (class "Default")
      (node (ref "C11") (pin "1") (pinfunction "1_1") (pintype "passive"))
      (node (ref "C6") (pin "1") (pinfunction "1_1") (pintype "passive"))
      (node (ref "F1") (pin "1") (pinfunction "1_1") (pintype "passive"))
      (node (ref "P10") (pin "10") (pinfunction "10_10") (pintype "passive"))
      (node (ref "P10") (pin "9") (pinfunction "9_9") (pintype "passive"))
      (node (ref "P14") (pin "A4") (pinfunction "VBUS_A4") (pintype "bidirectional"))
      (node (ref "P14") (pin "B4") (pinfunction "VBUS_B4") (pintype "bidirectional"))
      (node (ref "P15") (pin "A4") (pinfunction "VBUS_A4") (pintype "bidirectional"))
      (node (ref "P15") (pin "B4") (pinfunction "VBUS_B4") (pintype "bidirectional"))
      (node (ref "P3") (pin "10") (pinfunction "10_10") (pintype "passive"))
      (node (ref "P3") (pin "6") (pinfunction "6_6") (pintype "passive"))
      (node (ref "P3") (pin "8") (pinfunction "8_8") (pintype "passive"))
      (node (ref "P4") (pin "1") (pinfunction "+5V_1") (pintype "power_in"))
      (node (ref "P5") (pin "1") (pinfunction "+5V_1") (pintype "power_in"))
    )
    (net (code "107") (name "GND") (class "Default")
      (node (ref "C1") (pin "2") (pinfunction "2_2") (pintype "passive"))
      (node (ref "C10") (pin "1") (pinfunction "1_1") (pintype "passive"))
      (node (ref "C11") (pin "2") (pinfunction "2_2") (pintype "passive"))
      (node (ref "C12") (pin "1") (pinfunction "1_1") (pintype "passive"))
      (node (ref "C13") (pin "2") (pinfunction "2_2") (pintype "passive"))
      (node (ref "C14") (pin "1") (pinfunction "1_1") (pintype "passive"))
      (node (ref "C2") (pin "2") (pinfunction "2_2") (pintype "passive"))
      (node (ref "C3") (pin "2") (pinfunction "2_2") (pintype "passive"))
      (node (ref "C4") (pin "1") (pinfunction "1_1") (pintype "passive"))
      (node (ref "C42") (pin "1") (pinfunction "1_1") (pintype "passive"))
      (node (ref "C45") (pin "2") (pinfunction "2_2") (pintype "passive"))
      (node (ref "C46") (pin "2") (pinfunction "2_2") (pintype "passive"))
      (node (ref "C47") (pin "1") (pinfunction "1_1") (pintype "passive"))
      (node (ref "C5") (pin "2") (pinfunction "2_2") (pintype "passive"))
      (node (ref "C6") (pin "2") (pinfunction "2_2") (pintype "passive"))
      (node (ref "C7") (pin "1") (pinfunction "1_1") (pintype "passive"))
      (node (ref "C8") (pin "1") (pinfunction "1_1") (pintype "passive"))
      (node (ref "C9") (pin "1") (pinfunction "1_1") (pintype "passive"))
      (node (ref "P1") (pin "2") (pinfunction "2_2") (pintype "passive"))
      (node (ref "P10") (pin "5") (pinfunction "5_5") (pintype "passive"))
      (node (ref "P10") (pin "6") (pinfunction "6_6") (pintype "passive"))
      (node (ref "P14") (pin "A1") (pinfunction "GND_A1") (pintype "bidirectional"))
      (node (ref "P14") (pin "B1") (pinfunction "GND_B1") (pintype "bidirectional"))
      (node (ref "P15") (pin "A1") (pinfunction "GND_A1") (pintype "bidirectional"))
      (node (ref "P15") (pin "B1") (pinfunction "GND_B1") (pintype "bidirectional"))
      (node (ref "P2") (pin "8") (pintype "passive"))
      (node (ref "P3") (pin "1") (pinfunction "1_1") (pintype "passive"))
      (node (ref "P3") (pin "11") (pinfunction "11_11") (pintype "passive"))
      (node (ref "P3") (pin "13") (pinfunction "13_13") (pintype "passive"))
      (node (ref "P3") (pin "15") (pinfunction "15_15") (pintype "passive"))
      (node (ref "P3") (pin "2") (pinfunction "2_2") (pintype "passive"))
      (node (ref "P3") (pin "3") (pinfunction "3_3") (pintype "passive"))
      (node (ref "P3") (pin "4") (pinfunction "4_4") (pintype "passive"))
      (node (ref "P3") (pin "5") (pinfunction "5_5") (pintype "passive"))
      (node (ref "P3") (pin "7") (pinfunction "7_7") (pintype "passive"))
      (node (ref "P3") (pin "9") (pinfunction "9_9") (pintype "passive"))
      (node (ref "P4") (pin "4") (pinfunction "GND_4") (pintype "power_in"))
      (node (ref "P4") (pin "5") (pinfunction "GND_5") (pintype "power_in"))
      (node (ref "P4") (pin "6") (pinfunction "GND_6") (pintype "power_in"))
      (node (ref "P5") (pin "4") (pinfunction "GND_4") (pintype "power_in"))
      (node (ref "P5") (pin "5") (pinfunction "GND_5") (pintype "power_in"))
      (node (ref "P5") (pin "6") (pinfunction "GND_6") (pintype "power_in"))
      (node (ref "P6") (pin "25") (pinfunction "25_25") (pintype "passive"))
      (node (ref "P6") (pin "26") (pinfunction "26_26") (pintype "passive"))
      (node (ref "P6") (pin "27") (pinfunction "27_27") (pintype "passive"))
      (node (ref "P6") (pin "28") (pinfunction "28_28") (pintype "passive"))
      (node (ref "P6") (pin "5") (pinfunction "5_5") (pintype "passive"))
      (node (ref "P7") (pin "6") (pinfunction "6_6") (pintype "passive"))
      (node (ref "P9") (pin "1") (pinfunction "1_1") (pintype "passive"))
      (node (ref "P9") (pin "2") (pinfunction "2_2") (pintype "passive"))
      (node (ref "P9") (pin "39") (pinfunction "39_39") (pintype "passive"))
      (node (ref "P9") (pin "40") (pinfunction "40_40") (pintype "passive"))
      (node (ref "P9") (pin "41") (pinfunction "41_41") (pintype "passive"))
      (node (ref "P9") (pin "42") (pinfunction "42_42") (pintype "passive"))
      (node (ref "R17") (pin "1") (pinfunction "1_1") (pintype "passive"))
      (node (ref "R21") (pin "2") (pinfunction "2_2") (pintype "passive"))
      (node (ref "R22") (pin "2") (pinfunction "2_2") (pintype "passive"))
      (node (ref "R23") (pin "2") (pinfunction "2_2") (pintype "passive"))
      (node (ref "R24") (pin "2") (pinfunction "2_2") (pintype "passive"))
      (node (ref "R25") (pin "2") (pinfunction "2_2") (pintype "passive"))
      (node (ref "R26") (pin "2") (pinfunction "2_2") (pintype "passive"))
      (node (ref "R3") (pin "2") (pintype "passive"))
      (node (ref "R5") (pin "1") (pintype "passive"))
      (node (ref "S3") (pin "1") (pinfunction "1_1") (pintype "passive"))
      (node (ref "U1") (pin "1") (pinfunction "GND_1") (pintype "passive"))
      (node (ref "U2") (pin "10") (pinfunction "VSS_5_10") (pintype "power_in"))
      (node (ref "U2") (pin "19") (pinfunction "VSSA_19") (pintype "power_in"))
      (node (ref "U2") (pin "27") (pinfunction "VSS_4_27") (pintype "power_in"))
      (node (ref "U2") (pin "49") (pinfunction "VSS_1_49") (pintype "power_in"))
      (node (ref "U2") (pin "74") (pinfunction "VSS_2_74") (pintype "power_in"))
      (node (ref "U2") (pin "99") (pinfunction "VSS_3_99") (pintype "power_in"))
    )
    (net (code "108") (name "Net-(D1-K)") (class "Default")
      (node (ref "D1") (pin "2") (pinfunction "K_2") (pintype "passive"))
      (node (ref "R3") (pin "1") (pintype "passive"))
    )
    (net (code "109") (name "Net-(D3-A)") (class "Default")
      (node (ref "D3") (pin "1") (pinfunction "A_1") (pintype "passive"))
      (node (ref "R1") (pin "2") (pintype "passive"))
    )
    (net (code "110") (name "Net-(D4-A)") (class "Default")
      (node (ref "D4") (pin "1") (pinfunction "A_1") (pintype "passive"))
      (node (ref "R4") (pin "2") (pintype "passive"))
    )
    (net (code "111") (name "Net-(P2-Pad9)") (class "Default")
      (node (ref "P2") (pin "9") (pintype "passive"))
      (node (ref "R8") (pin "2") (pintype "passive"))
    )
    (net (code "112") (name "Net-(P2-Pad12)") (class "Default")
      (node (ref "P2") (pin "12") (pintype "passive"))
      (node (ref "R9") (pin "2") (pintype "passive"))
    )
    (net (code "113") (name "Net-(P14-CC-PadA5)") (class "Default")
      (node (ref "P14") (pin "A5") (pinfunction "CC_A5") (pintype "bidirectional"))
      (node (ref "R25") (pin "1") (pinfunction "1_1") (pintype "passive"))
    )
    (net (code "114") (name "Net-(P14-CC-PadB5)") (class "Default")
      (node (ref "P14") (pin "B5") (pinfunction "CC_B5") (pintype "bidirectional"))
      (node (ref "R26") (pin "1") (pinfunction "1_1") (pintype "passive"))
    )
    (net (code "115") (name "Net-(P15-CC-PadA5)") (class "Default")
      (node (ref "P15") (pin "A5") (pinfunction "CC_A5") (pintype "bidirectional"))
      (node (ref "R23") (pin "1") (pinfunction "1_1") (pintype "passive"))
    )
    (net (code "116") (name "Net-(P15-CC-PadB5)") (class "Default")
      (node (ref "P15") (pin "B5") (pinfunction "CC_B5") (pintype "bidirectional"))
      (node (ref "R24") (pin "1") (pinfunction "1_1") (pintype "passive"))
    )
    (net (code "117") (name "Net-(R5-Pad2)") (class "Default")
      (node (ref "R5") (pin "2") (pintype "passive"))
      (node (ref "S2") (pin "2") (pinfunction "2_2") (pintype "passive"))
    )
    (net (code "118") (name "Net-(R20-Pad2)") (class "Default")
      (node (ref "R20") (pin "2") (pinfunction "2_2") (pintype "passive"))
      (node (ref "S4") (pin "2") (pinfunction "2_2") (pintype "passive"))
    )
    (net (code "119") (name "Net-(S1-COMMON)") (class "Default")
      (node (ref "F1") (pin "2") (pinfunction "2_2") (pintype "passive"))
      (node (ref "S1") (pin "1") (pinfunction "COMMON_1") (pintype "passive"))
    )
    (net (code "120") (name "Net-(S1-NC)") (class "Default")
      (node (ref "C1") (pin "1") (pinfunction "1_1") (pintype "passive"))
      (node (ref "S1") (pin "2") (pinfunction "NC_2") (pintype "passive"))
      (node (ref "U1") (pin "3") (pinfunction "Vin_3") (pintype "passive"))
    )
    (net (code "121") (name "unconnected-(P2-Pad7)") (class "Default")
      (node (ref "P2") (pin "7") (pintype "passive"))
    )
    (net (code "122") (name "unconnected-(P14-RFU1-PadA8)") (class "Default")
      (node (ref "P14") (pin "A8") (pinfunction "RFU1_A8") (pintype "bidirectional+no_connect"))
    )
    (net (code "123") (name "unconnected-(P14-RFU1-PadB8)") (class "Default")
      (node (ref "P14") (pin "B8") (pinfunction "RFU1_B8") (pintype "bidirectional+no_connect"))
    )
    (net (code "124") (name "unconnected-(P15-RFU1-PadA8)") (class "Default")
      (node (ref "P15") (pin "A8") (pinfunction "RFU1_A8") (pintype "bidirectional+no_connect"))
    )
    (net (code "125") (name "unconnected-(P15-RFU1-PadB8)") (class "Default")
      (node (ref "P15") (pin "B8") (pinfunction "RFU1_B8") (pintype "bidirectional+no_connect"))
    )
    (net (code "126") (name "unconnected-(S1-NO-Pad3)") (class "Default")
      (node (ref "S1") (pin "3") (pinfunction "NO_3") (pintype "passive"))
    )
  )
)
